# Kicker.net
KiCad netlist of a schematic drawn in Altium Designer
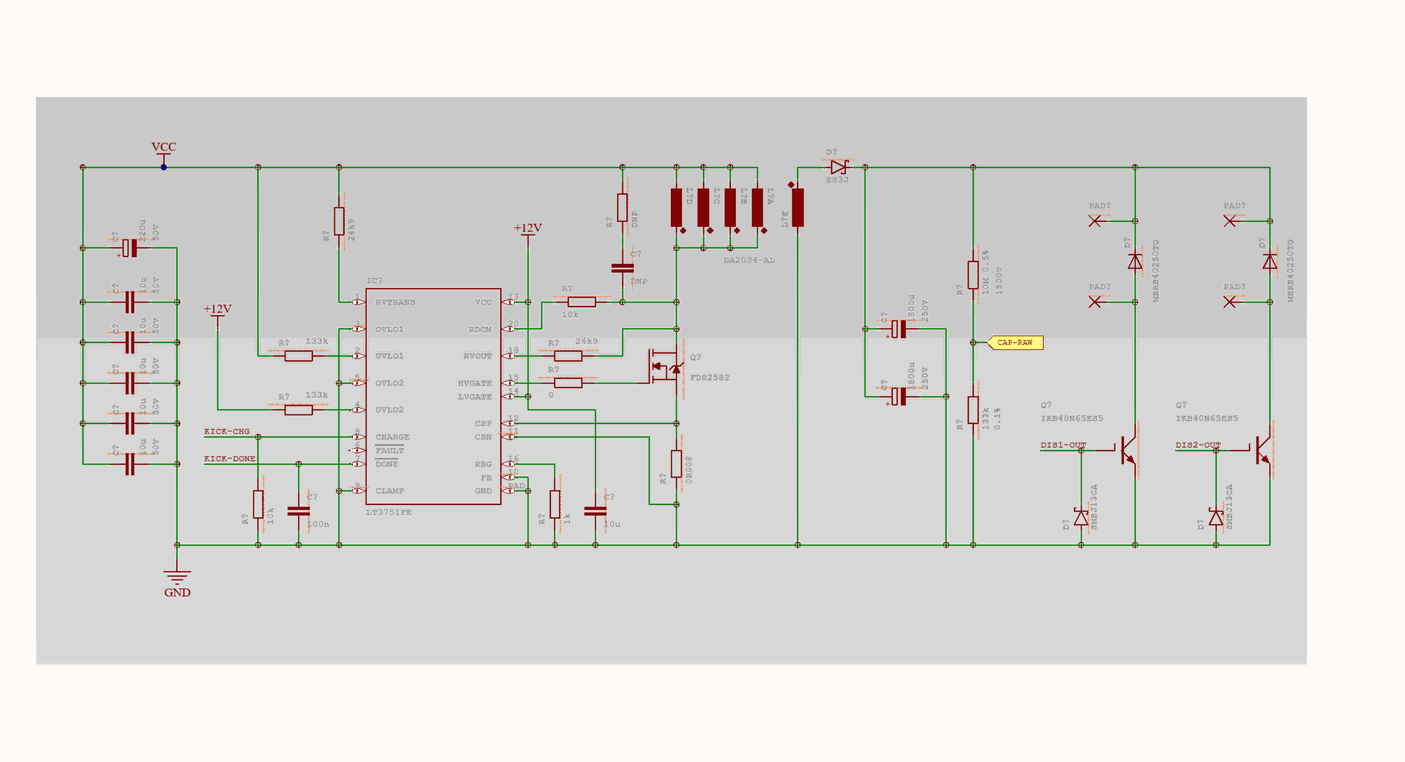
[diagram p0: Kicker.SchDoc, left]
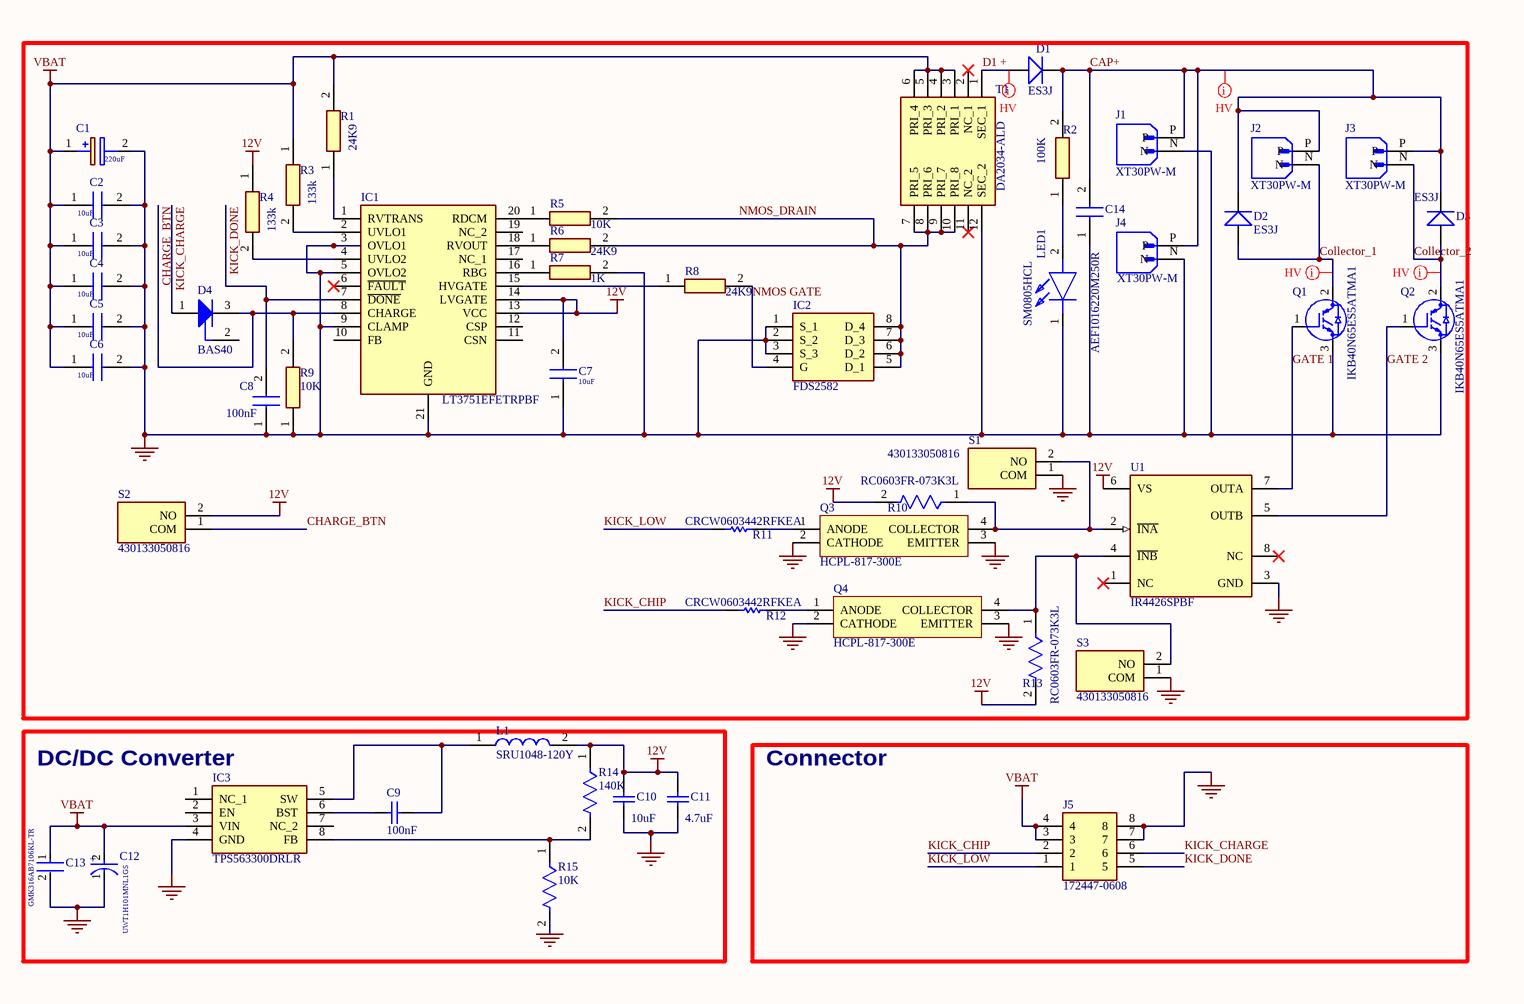
[diagram p1: Kicker.SchDoc, right]

(export (version "E")
  (design (tool "Eeschema 10.0.6"))
  (components
    (comp (ref "C1")
      (value "220uF")
      (footprint "SamacSys:CAPAE1030X1050N")
      (description "Capacitor Polarised")
      (fields
        (field (name "MANUFACTURER_PART_NUMBER") "865080657018")
        (field (name "MOUSER PART NUMBER") "710-865080657018")
      )
      (libsource (lib "*") (part "865080657018"))
    )
    (comp (ref "C2")
      (value "10uF")
      (footprint "SamacSys:CAPC2012X145N")
      (description "Capacitor 10u")
      (fields
        (field (name "MANUFACTURER_PART_NUMBER") "GRM21BR61H106KE43L")
        (field (name "MOUSER PART NUMBER") "81-GRM21BR61H106KE3L")
      )
      (libsource (lib "*") (part "GRM21BR61H106KE43L"))
    )
    (comp (ref "C3")
      (value "10uF")
      (footprint "SamacSys:CAPC2012X145N")
      (description "Capacitor 10u")
      (fields
        (field (name "MANUFACTURER_PART_NUMBER") "GRM21BR61H106KE43L")
        (field (name "MOUSER PART NUMBER") "81-GRM21BR61H106KE3L")
      )
      (libsource (lib "*") (part "GRM21BR61H106KE43L"))
    )
    (comp (ref "C4")
      (value "10uF")
      (footprint "SamacSys:CAPC2012X145N")
      (description "Capacitor 10u")
      (fields
        (field (name "MANUFACTURER_PART_NUMBER") "GRM21BR61H106KE43L")
        (field (name "MOUSER PART NUMBER") "81-GRM21BR61H106KE3L")
      )
      (libsource (lib "*") (part "GRM21BR61H106KE43L"))
    )
    (comp (ref "C5")
      (value "10uF")
      (footprint "SamacSys:CAPC2012X145N")
      (description "Capacitor 10u")
      (fields
        (field (name "MANUFACTURER_PART_NUMBER") "GRM21BR61H106KE43L")
        (field (name "MOUSER PART NUMBER") "81-GRM21BR61H106KE3L")
      )
      (libsource (lib "*") (part "GRM21BR61H106KE43L"))
    )
    (comp (ref "C6")
      (value "10uF")
      (footprint "SamacSys:CAPC2012X145N")
      (description "Capacitor 10u")
      (fields
        (field (name "MANUFACTURER_PART_NUMBER") "GRM21BR61H106KE43L")
        (field (name "MOUSER PART NUMBER") "81-GRM21BR61H106KE3L")
      )
      (libsource (lib "*") (part "GRM21BR61H106KE43L"))
    )
    (comp (ref "C7")
      (value "10uF")
      (footprint "SamacSys:CAPC2012X145N")
      (description "Capacitor 10u")
      (fields
        (field (name "MANUFACTURER_PART_NUMBER") "GRM21BR61H106KE43L")
        (field (name "MOUSER PART NUMBER") "81-GRM21BR61H106KE3L")
      )
      (libsource (lib "*") (part "GRM21BR61H106KE43L"))
    )
    (comp (ref "C8")
      (value "100nF")
      (footprint "SamacSys:CAPC1608X95N")
      (description "Capacitor")
      (fields
        (field (name "MANUFACTURER_PART_NUMBER") "C0603C104K1RACAUTO")
        (field (name "MOUSER PART NUMBER") "80-C0603C104K1RAUTO")
      )
      (libsource (lib "*") (part "C0603C104K1RACAUTO"))
    )
    (comp (ref "C9")
      (value "100nF")
      (footprint "CAPC0805(2012)155_L")
      (description "CAP 10uF 6.3V ±10% 0805 (2012 Metric) Thickness 1.55mm SMD")
      (fields (field (name "TOLERANCE") "Â±10%"))
      (libsource (lib "Altium Content Vault") (part "CAP"))
    )
    (comp (ref "C10")
      (value "10uF")
      (footprint "CAPC0805(2012)155_L")
      (description "CAP 10uF 6.3V ±10% 0805 (2012 Metric) Thickness 1.55mm SMD")
      (fields (field (name "TOLERANCE") "Â±10%"))
      (libsource (lib "Altium Content Vault") (part "CAP"))
    )
    (comp (ref "C11")
      (value "4.7uF")
      (footprint "CAPC0805(2012)155_L")
      (description "CAP 10uF 6.3V ±10% 0805 (2012 Metric) Thickness 1.55mm SMD")
      (fields (field (name "TOLERANCE") "Â±10%"))
      (libsource (lib "Altium Content Vault") (part "CAP"))
    )
    (comp (ref "C12")
      (value "UWT1H101MNL1GS")
      (footprint "FP-UWT1H101MNL1GS-MFG")
      (description "CAP ALUM 100UF 20% 50V SMD")
      (fields (field (name "TOLERANCE") "20%") (field (name "VOLTAGE") "50V"))
      (libsource (lib "Altium Content Vault") (part "203bc49f2ac43e59fd269a8c329ed05"))
    )
    (comp (ref "C13")
      (value "GMK316AB7106KL-TR")
      (footprint "FP-1206-L_3_2_0_2-W_1_6_0-IPC_C")
      (description "None")
      (fields (field (name "TOLERANCE") "10%"))
      (libsource (lib "Altium Content Vault") (part "b4654b650e69147ec39a6b967a45e02"))
    )
    (comp (ref "C14")
      (value "AEF1016220M250R")
      (footprint "roboime:CAPAE1030X1700N")
      (description "Capacitor")
      (fields (field (name "MOUSER PART NUMBER") "581-AEF1016220M250R"))
      (libsource (lib "roboime") (part "AEF1016220M250R"))
    )
    (comp (ref "D1") (value "ES3J") (footprint "Diode") (libsource (lib "roboime") (part "ES3J")))
    (comp (ref "D2") (value "ES3J") (footprint "Diode") (libsource (lib "roboime") (part "ES3J")))
    (comp (ref "D3") (value "ES3J") (footprint "Diode") (libsource (lib "roboime") (part "ES3J")))
    (comp (ref "D4")
      (value "BAS40")
      (footprint "INF-SOT23_L")
      (description "Silicon Schottky Diode, -55 to 150 degC, SOT23, Reel, Green")
      (fields (field (name "MANUFACTURER") "Infineon"))
      (libsource (lib "Altium Content Vault") (part "INF-D_A1K3-3"))
    )
    (comp (ref "IC1")
      (value "LT3751EFETRPBF")
      (footprint "SamacSys:SOP65P640X120-21N")
      (description "Integrated Circuit")
      (libsource (lib "*") (part "LT3751EFETRPBF"))
    )
    (comp (ref "IC2")
      (value "FDS2582")
      (footprint "SamacSys:SOIC127P600X175-8N")
      (description "Integrated Circuit")
      (fields (field (name "MOUSER PART NUMBER") "512-FDS2582"))
      (libsource (lib "*") (part "FDS2582"))
    )
    (comp (ref "IC3")
      (value "TPS563300DRLR")
      (footprint "roboime:SOTFL50P160X60-8N")
      (description "Integrated Circuit")
      (fields (field (name "MOUSER PART NUMBER") "595-TPS563300DRLR"))
      (libsource (lib "roboime") (part "TPS563300DRLR"))
    )
    (comp (ref "J1")
      (value "XT30PW-M")
      (footprint "AMASS_XT30PW-M")
      (description "Socket; DC supply; XT30; male; PIN: 2; on PCBs; THT; Colour: yellow")
      (fields (field (name "MF") "AMASS"))
      (libsource (lib "roboime") (part "XT30PW-M"))
    )
    (comp (ref "J2")
      (value "XT30PW-M")
      (footprint "AMASS_XT30PW-M")
      (description "Socket; DC supply; XT30; male; PIN: 2; on PCBs; THT; Colour: yellow")
      (fields (field (name "MF") "AMASS"))
      (libsource (lib "roboime") (part "XT30PW-M"))
    )
    (comp (ref "J3")
      (value "XT30PW-M")
      (footprint "AMASS_XT30PW-M")
      (description "Socket; DC supply; XT30; male; PIN: 2; on PCBs; THT; Colour: yellow")
      (fields (field (name "MF") "AMASS"))
      (libsource (lib "roboime") (part "XT30PW-M"))
    )
    (comp (ref "J4")
      (value "XT30PW-M")
      (footprint "AMASS_XT30PW-M")
      (description "Socket; DC supply; XT30; male; PIN: 2; on PCBs; THT; Colour: yellow")
      (fields (field (name "MF") "AMASS"))
      (libsource (lib "roboime") (part "XT30PW-M"))
    )
    (comp (ref "J5")
      (value "172447-0608")
      (footprint "roboime:172447-YY08")
      (description "Connector")
      (fields (field (name "MOUSER PART NUMBER") "538-172447-0608"))
      (libsource (lib "roboime") (part "172447-0608"))
    )
    (comp (ref "L1")
      (value "SRU1048-120Y")
      (footprint "roboime:INDP100100X51N")
      (description "Inductor 12uH 4A")
      (fields
        (field (name "MANUFACTURER_PART_NUMBER") "CLF7045T-4R7N-D")
        (field (name "MOUSER PART NUMBER") "810-CLF7045T-4R7N-D")
      )
      (libsource (lib "roboime") (part "SRU1048-120Y"))
    )
    (comp (ref "LED1")
      (value "SM0805HCL")
      (footprint "roboime:LEDC2012X105N")
      (description "LED")
      (fields (field (name "MOUSER PART NUMBER") "749-SM0805HCL"))
      (libsource (lib "roboime") (part "SM0805HCL"))
    )
    (comp (ref "Q1")
      (value "IKB40N65ES5ATMA1")
      (footprint "roboime:BTS141TCBUMA1")
      (description "Transistor IGBT")
      (fields (field (name "MOUSER PART NUMBER") "726-IKB40N65ES5ATMA1"))
      (libsource (lib "roboime") (part "IKB40N65ES5ATMA1"))
    )
    (comp (ref "Q2")
      (value "IKB40N65ES5ATMA1")
      (footprint "roboime:BTS141TCBUMA1")
      (description "Transistor IGBT")
      (fields (field (name "MOUSER PART NUMBER") "726-IKB40N65ES5ATMA1"))
      (libsource (lib "roboime") (part "IKB40N65ES5ATMA1"))
    )
    (comp (ref "Q3")
      (value "HCPL-817-300E")
      (footprint "roboime:HCPL-817-300")
      (libsource (lib "roboime") (part "HCPL-817-300E"))
    )
    (comp (ref "Q4")
      (value "HCPL-817-300E")
      (footprint "roboime:HCPL-817-300")
      (libsource (lib "roboime") (part "HCPL-817-300E"))
    )
    (comp (ref "R1")
      (value "24K9")
      (footprint "SamacSys:ERJS03J155V")
      (description "Resistor")
      (fields
        (field (name "MANUFACTURER_PART_NUMBER") "ERJ-U03F2492V")
        (field (name "MOUSER PART NUMBER") "667-ERJ-U03F2492V")
      )
      (libsource (lib "*") (part "ERJ-U03F2492V"))
    )
    (comp (ref "R2")
      (value "100K")
      (footprint "SamacSys:RESC1608X55N")
      (description "Resistor")
      (fields
        (field (name "MANUFACTURER_PART_NUMBER") "CPF0603F100KC1")
        (field (name "MOUSER PART NUMBER") "279-CPF0603F100KC1")
      )
      (libsource (lib "*") (part "CPF0603F100KC1"))
    )
    (comp (ref "R3")
      (value "133k")
      (footprint "SamacSys:ERJUP3")
      (description "Resistor")
      (fields
        (field (name "MANUFACTURER_PART_NUMBER") "ERJ-UP3F1333V")
        (field (name "MOUSER PART NUMBER") "667-ERJ-UP3F1333V")
      )
      (libsource (lib "*") (part "ERJ-UP3F1333V"))
    )
    (comp (ref "R4")
      (value "133k")
      (footprint "SamacSys:ERJUP3")
      (description "Resistor")
      (fields
        (field (name "MANUFACTURER_PART_NUMBER") "ERJ-UP3F1333V")
        (field (name "MOUSER PART NUMBER") "667-ERJ-UP3F1333V")
      )
      (libsource (lib "*") (part "ERJ-UP3F1333V"))
    )
    (comp (ref "R5")
      (value "10K")
      (footprint "SamacSys:RESC1608X55N")
      (description "Resistor")
      (fields
        (field (name "MANUFACTURER_PART_NUMBER") "ERJ-U3RD1002V")
        (field (name "MOUSER PART NUMBER") "667-ERJ-U3RD1002V")
      )
      (libsource (lib "") (part "ERJ-U3RD1002V_1"))
    )
    (comp (ref "R6")
      (value "24K9")
      (footprint "SamacSys:ERJS03J155V")
      (description "Resistor")
      (fields
        (field (name "MANUFACTURER_PART_NUMBER") "ERJ-U03F2492V")
        (field (name "MOUSER PART NUMBER") "667-ERJ-U03F2492V")
      )
      (libsource (lib "") (part "ERJ-U03F2492V_1"))
    )
    (comp (ref "R7")
      (value "1K")
      (footprint "SamacSys:RESC1608X55N")
      (description "Resistor")
      (fields
        (field (name "MANUFACTURER_PART_NUMBER") "CHP0603QFX-1001ELF")
        (field (name "MOUSER PART NUMBER") "652-CHP0603QFX-1001E")
      )
      (libsource (lib "*") (part "CHP0603QFX-1001ELF"))
    )
    (comp (ref "R8")
      (value "24K9")
      (footprint "SamacSys:ERJS03J155V")
      (description "Resistor")
      (fields
        (field (name "MANUFACTURER_PART_NUMBER") "ERJ-U03F2492V")
        (field (name "MOUSER PART NUMBER") "667-ERJ-U03F2492V")
      )
      (libsource (lib "") (part "ERJ-U03F2492V_1"))
    )
    (comp (ref "R9")
      (value "10K")
      (footprint "SamacSys:RESC1608X55N")
      (description "Resistor")
      (fields
        (field (name "MANUFACTURER_PART_NUMBER") "ERJ-U3RD1002V")
        (field (name "MOUSER PART NUMBER") "667-ERJ-U3RD1002V")
      )
      (libsource (lib "*") (part "ERJ-U3RD1002V"))
    )
    (comp (ref "R10")
      (value "RC0603FR-073K3L")
      (footprint "FP-RC0603-0_55-MFG")
      (fields (field (name "TOLERANCE") "1%"))
      (libsource (lib "Altium Content Vault") (part "1029c3af85768c4190bb7ad29bc67b5"))
    )
    (comp (ref "R11")
      (value "CRCW0603442RFKEA")
      (footprint "RESC1609X50X30ML10T20")
      (fields (field (name "MANUFACTURER") "Vishay Dale"))
      (libsource (lib "Altium Content Vault") (part "RES"))
    )
    (comp (ref "R12")
      (value "CRCW0603442RFKEA")
      (footprint "RESC1609X50X30ML10T20")
      (fields (field (name "MANUFACTURER") "Vishay Dale"))
      (libsource (lib "Altium Content Vault") (part "RES"))
    )
    (comp (ref "R13")
      (value "RC0603FR-073K3L")
      (footprint "FP-RC0603-0_55-MFG")
      (fields (field (name "TOLERANCE") "1%"))
      (libsource (lib "Altium Content Vault") (part "1029c3af85768c4190bb7ad29bc67b5"))
    )
    (comp (ref "R14")
      (value "140K")
      (footprint "FP-CRCW0805-e3-MFG")
      (description "RES Thick Film, 30kΩ, 1%, 0.125W, 100ppm/°C, 0805")
      (fields (field (name "TOLERANCE") "1%"))
      (libsource (lib "Altium Content Vault") (part "1029c3af85768c4190bb7ad29bc67b5"))
    )
    (comp (ref "R15")
      (value "10K")
      (footprint "FP-CRCW0805-e3-IPC_A")
      (description "RES Thick Film, 10kΩ, 1%, 0.125W, 100ppm/°C, 0805")
      (fields (field (name "TOLERANCE") "1%"))
      (libsource (lib "Altium Content Vault") (part "1029c3af85768c4190bb7ad29bc67b5"))
    )
    (comp (ref "S1")
      (value "430133050816")
      (footprint "SamacSys:430133050816")
      (description "Switch")
      (fields (field (name "MOUSER PART NUMBER") "710-430133050816"))
      (libsource (lib "roboime") (part "430133050816"))
    )
    (comp (ref "S2")
      (value "430133050816")
      (footprint "SamacSys:430133050816")
      (description "Switch")
      (fields (field (name "MOUSER PART NUMBER") "710-430133050816"))
      (libsource (lib "roboime") (part "430133050816"))
    )
    (comp (ref "S3")
      (value "430133050816")
      (footprint "SamacSys:430133050816")
      (description "Switch")
      (fields (field (name "MOUSER PART NUMBER") "710-430133050816"))
      (libsource (lib "roboime") (part "430133050816"))
    )
    (comp (ref "T1")
      (value "DA2034-ALD")
      (footprint "SamacSys:SOP300P3000X1143-12N")
      (description "Transformer")
      (fields (field (name "MOUSER PART NUMBER") "994-DA2034-ALD"))
      (libsource (lib "*") (part "DA2034-ALD"))
    )
    (comp (ref "U1")
      (value "IR4426SPBF")
      (footprint "FP-PG-DSO-8-MFG")
      (description "IC GATE DRVR LOW-SIDE 8SOIC")
      (libsource (lib "Altium Content Vault") (part "283eb03ded679e5ad24fb8acc9adf19"))
    )
  )
  (nets
    (net (code "1") (name "/CAP+") (class "Default")
      (node (ref "C14") (pin "2") (pinfunction "-_2") (pintype "passive"))
      (node (ref "D1") (pin "D1+") (pinfunction "D1+_D1+") (pintype "passive"))
      (node (ref "D2") (pin "D1+") (pinfunction "D1+_D1+") (pintype "passive"))
      (node (ref "D3") (pin "D1+") (pinfunction "D1+_D1+") (pintype "passive"))
      (node (ref "J1") (pin "P") (pinfunction "P_P") (pintype "power_in"))
      (node (ref "J2") (pin "P") (pinfunction "P_P") (pintype "power_in"))
      (node (ref "J3") (pin "P") (pinfunction "P_P") (pintype "power_in"))
      (node (ref "J4") (pin "P") (pinfunction "P_P") (pintype "power_in"))
      (node (ref "R2") (pin "2") (pinfunction "2_2") (pintype "passive"))
    )
    (net (code "2") (name "/CHARGE_BTN") (class "Default")
      (node (ref "D4") (pin "3") (pinfunction "K_3") (pintype "passive"))
      (node (ref "IC1") (pin "8") (pinfunction "CHARGE_8") (pintype "passive"))
      (node (ref "R9") (pin "2") (pinfunction "2_2") (pintype "passive"))
      (node (ref "S2") (pin "1") (pinfunction "COM_1") (pintype "passive"))
    )
    (net (code "3") (name "/Collector_1") (class "Default")
      (node (ref "D2") (pin "D1-") (pinfunction "D1-_D1-") (pintype "passive"))
      (node (ref "J2") (pin "N") (pinfunction "N_N") (pintype "power_in"))
      (node (ref "Q1") (pin "2") (pinfunction "C_2") (pintype "passive"))
    )
    (net (code "4") (name "/Collector_2") (class "Default")
      (node (ref "D3") (pin "D1-") (pinfunction "D1-_D1-") (pintype "passive"))
      (node (ref "J3") (pin "N") (pinfunction "N_N") (pintype "power_in"))
      (node (ref "Q2") (pin "2") (pinfunction "C_2") (pintype "passive"))
    )
    (net (code "5") (name "/D1 +") (class "Default")
      (node (ref "D1") (pin "D1-") (pinfunction "D1-_D1-") (pintype "passive"))
      (node (ref "T1") (pin "1") (pinfunction "SEC_1_1") (pintype "passive"))
    )
    (net (code "6") (name "/GATE 1") (class "Default")
      (node (ref "Q1") (pin "1") (pinfunction "G_1") (pintype "passive"))
      (node (ref "U1") (pin "7") (pinfunction "OUTA_7") (pintype "passive"))
    )
    (net (code "7") (name "/GATE 2") (class "Default")
      (node (ref "Q2") (pin "1") (pinfunction "G_1") (pintype "passive"))
      (node (ref "U1") (pin "5") (pinfunction "OUTB_5") (pintype "passive"))
    )
    (net (code "8") (name "/KICK_CHARGE") (class "Default")
      (node (ref "D4") (pin "1") (pinfunction "A_1") (pintype "passive"))
      (node (ref "J5") (pin "6") (pinfunction "6_6") (pintype "passive"))
    )
    (net (code "9") (name "/KICK_CHIP") (class "Default")
      (node (ref "J5") (pin "2") (pinfunction "2_2") (pintype "passive"))
      (node (ref "R12") (pin "1") (pinfunction "1_1") (pintype "passive"))
    )
    (net (code "10") (name "/KICK_DONE") (class "Default")
      (node (ref "C8") (pin "2") (pinfunction "2_2") (pintype "passive"))
      (node (ref "IC1") (pin "7") (pinfunction "~{DONE}_7") (pintype "passive"))
      (node (ref "J5") (pin "5") (pinfunction "5_5") (pintype "passive"))
    )
    (net (code "11") (name "/KICK_LOW") (class "Default")
      (node (ref "J5") (pin "1") (pinfunction "1_1") (pintype "passive"))
      (node (ref "R11") (pin "1") (pinfunction "1_1") (pintype "passive"))
    )
    (net (code "12") (name "/NMOS GATE") (class "Default")
      (node (ref "IC2") (pin "4") (pinfunction "G_4") (pintype "passive"))
      (node (ref "R8") (pin "2") (pinfunction "2_2") (pintype "passive"))
    )
    (net (code "13") (name "/NMOS_DRAIN") (class "Default")
      (node (ref "IC2") (pin "5") (pinfunction "D_1_5") (pintype "passive"))
      (node (ref "IC2") (pin "6") (pinfunction "D_2_6") (pintype "passive"))
      (node (ref "IC2") (pin "7") (pinfunction "D_3_7") (pintype "passive"))
      (node (ref "IC2") (pin "8") (pinfunction "D_4_8") (pintype "passive"))
      (node (ref "R5") (pin "2") (pinfunction "2_2") (pintype "passive"))
      (node (ref "R6") (pin "2") (pinfunction "2_2") (pintype "passive"))
      (node (ref "T1") (pin "10") (pinfunction "PRI_8_10") (pintype "passive"))
      (node (ref "T1") (pin "7") (pinfunction "PRI_5_7") (pintype "passive"))
      (node (ref "T1") (pin "8") (pinfunction "PRI_6_8") (pintype "passive"))
      (node (ref "T1") (pin "9") (pinfunction "PRI_7_9") (pintype "passive"))
    )
    (net (code "14") (name "12V") (class "Default")
      (node (ref "C10") (pin "2") (pinfunction "2_2") (pintype "passive"))
      (node (ref "C11") (pin "2") (pinfunction "2_2") (pintype "passive"))
      (node (ref "C7") (pin "2") (pinfunction "2_2") (pintype "passive"))
      (node (ref "IC1") (pin "13") (pinfunction "VCC_13") (pintype "passive"))
      (node (ref "IC1") (pin "14") (pinfunction "LVGATE_14") (pintype "passive"))
      (node (ref "L1") (pin "2") (pinfunction "2_2") (pintype "passive"))
      (node (ref "R10") (pin "2") (pinfunction "2_2") (pintype "passive"))
      (node (ref "R13") (pin "2") (pinfunction "2_2") (pintype "passive"))
      (node (ref "R14") (pin "1") (pinfunction "1_1") (pintype "passive"))
      (node (ref "R4") (pin "1") (pinfunction "1_1") (pintype "passive"))
      (node (ref "S2") (pin "2") (pinfunction "NO_2") (pintype "passive"))
      (node (ref "U1") (pin "6") (pinfunction "VS_6") (pintype "power_in"))
    )
    (net (code "15") (name "GND") (class "Default")
      (node (ref "C1") (pin "2") (pinfunction "-_2") (pintype "passive"))
      (node (ref "C10") (pin "1") (pinfunction "1_1") (pintype "passive"))
      (node (ref "C11") (pin "1") (pinfunction "1_1") (pintype "passive"))
      (node (ref "C12") (pin "1") (pinfunction "C_1") (pintype "passive"))
      (node (ref "C13") (pin "2") (pinfunction "2_2") (pintype "passive"))
      (node (ref "C14") (pin "1") (pinfunction "+_1") (pintype "passive"))
      (node (ref "C2") (pin "2") (pinfunction "2_2") (pintype "passive"))
      (node (ref "C3") (pin "2") (pinfunction "2_2") (pintype "passive"))
      (node (ref "C4") (pin "2") (pinfunction "2_2") (pintype "passive"))
      (node (ref "C5") (pin "2") (pinfunction "2_2") (pintype "passive"))
      (node (ref "C6") (pin "2") (pinfunction "2_2") (pintype "passive"))
      (node (ref "C7") (pin "1") (pinfunction "1_1") (pintype "passive"))
      (node (ref "C8") (pin "1") (pinfunction "1_1") (pintype "passive"))
      (node (ref "IC1") (pin "21") (pinfunction "GND_21") (pintype "passive"))
      (node (ref "IC1") (pin "3") (pinfunction "OVLO1_3") (pintype "passive"))
      (node (ref "IC1") (pin "5") (pinfunction "OVLO2_5") (pintype "passive"))
      (node (ref "IC1") (pin "9") (pinfunction "CLAMP_9") (pintype "passive"))
      (node (ref "IC2") (pin "1") (pinfunction "S_1_1") (pintype "passive"))
      (node (ref "IC2") (pin "2") (pinfunction "S_2_2") (pintype "passive"))
      (node (ref "IC2") (pin "3") (pinfunction "S_3_3") (pintype "passive"))
      (node (ref "IC3") (pin "4") (pinfunction "GND_4") (pintype "passive"))
      (node (ref "J1") (pin "N") (pinfunction "N_N") (pintype "power_in"))
      (node (ref "J4") (pin "N") (pinfunction "N_N") (pintype "power_in"))
      (node (ref "J5") (pin "7") (pinfunction "7_7") (pintype "passive"))
      (node (ref "J5") (pin "8") (pinfunction "8_8") (pintype "passive"))
      (node (ref "LED1") (pin "1") (pinfunction "K_1") (pintype "passive"))
      (node (ref "Q1") (pin "3") (pinfunction "E_3") (pintype "passive"))
      (node (ref "Q2") (pin "3") (pinfunction "E_3") (pintype "passive"))
      (node (ref "Q3") (pin "2") (pinfunction "CATHODE_2") (pintype "passive"))
      (node (ref "Q3") (pin "3") (pinfunction "EMITTER_3") (pintype "passive"))
      (node (ref "Q4") (pin "2") (pinfunction "CATHODE_2") (pintype "passive"))
      (node (ref "Q4") (pin "3") (pinfunction "EMITTER_3") (pintype "passive"))
      (node (ref "R15") (pin "2") (pinfunction "2_2") (pintype "passive"))
      (node (ref "R7") (pin "2") (pinfunction "2_2") (pintype "passive"))
      (node (ref "R9") (pin "1") (pinfunction "1_1") (pintype "passive"))
      (node (ref "S1") (pin "1") (pinfunction "COM_1") (pintype "passive"))
      (node (ref "S3") (pin "1") (pinfunction "COM_1") (pintype "passive"))
      (node (ref "T1") (pin "12") (pinfunction "SEC_2_12") (pintype "passive"))
      (node (ref "U1") (pin "3") (pinfunction "GND_3") (pintype "power_in"))
    )
    (net (code "16") (name "Net-(IC1-HVGATE)") (class "Default")
      (node (ref "IC1") (pin "15") (pinfunction "HVGATE_15") (pintype "passive"))
      (node (ref "R8") (pin "1") (pinfunction "1_1") (pintype "passive"))
    )
    (net (code "17") (name "Net-(IC1-RBG)") (class "Default")
      (node (ref "IC1") (pin "16") (pinfunction "RBG_16") (pintype "passive"))
      (node (ref "R7") (pin "1") (pinfunction "1_1") (pintype "passive"))
    )
    (net (code "18") (name "Net-(IC1-RDCM)") (class "Default")
      (node (ref "IC1") (pin "20") (pinfunction "RDCM_20") (pintype "passive"))
      (node (ref "R5") (pin "1") (pinfunction "1_1") (pintype "passive"))
    )
    (net (code "19") (name "Net-(IC1-RVOUT)") (class "Default")
      (node (ref "IC1") (pin "18") (pinfunction "RVOUT_18") (pintype "passive"))
      (node (ref "R6") (pin "1") (pinfunction "1_1") (pintype "passive"))
    )
    (net (code "20") (name "Net-(IC1-RVTRANS)") (class "Default")
      (node (ref "IC1") (pin "1") (pinfunction "RVTRANS_1") (pintype "passive"))
      (node (ref "R1") (pin "1") (pinfunction "1_1") (pintype "passive"))
    )
    (net (code "21") (name "Net-(IC1-UVLO1)") (class "Default")
      (node (ref "IC1") (pin "2") (pinfunction "UVLO1_2") (pintype "passive"))
      (node (ref "R3") (pin "2") (pinfunction "2_2") (pintype "passive"))
    )
    (net (code "22") (name "Net-(IC1-UVLO2)") (class "Default")
      (node (ref "IC1") (pin "4") (pinfunction "UVLO2_4") (pintype "passive"))
      (node (ref "R4") (pin "2") (pinfunction "2_2") (pintype "passive"))
    )
    (net (code "23") (name "Net-(IC3-BST)") (class "Default")
      (node (ref "C9") (pin "2") (pinfunction "2_2") (pintype "passive"))
      (node (ref "IC3") (pin "6") (pinfunction "BST_6") (pintype "passive"))
    )
    (net (code "24") (name "Net-(IC3-FB)") (class "Default")
      (node (ref "IC3") (pin "8") (pinfunction "FB_8") (pintype "passive"))
      (node (ref "R14") (pin "2") (pinfunction "2_2") (pintype "passive"))
      (node (ref "R15") (pin "1") (pinfunction "1_1") (pintype "passive"))
    )
    (net (code "25") (name "Net-(IC3-SW)") (class "Default")
      (node (ref "C9") (pin "1") (pinfunction "1_1") (pintype "passive"))
      (node (ref "IC3") (pin "5") (pinfunction "SW_5") (pintype "passive"))
      (node (ref "L1") (pin "1") (pinfunction "1_1") (pintype "passive"))
    )
    (net (code "26") (name "Net-(LED1-A)") (class "Default")
      (node (ref "LED1") (pin "2") (pinfunction "A_2") (pintype "passive"))
      (node (ref "R2") (pin "1") (pinfunction "1_1") (pintype "passive"))
    )
    (net (code "27") (name "Net-(Q3-ANODE)") (class "Default")
      (node (ref "Q3") (pin "1") (pinfunction "ANODE_1") (pintype "passive"))
      (node (ref "R11") (pin "2") (pinfunction "2_2") (pintype "passive"))
    )
    (net (code "28") (name "Net-(Q3-COLLECTOR)") (class "Default")
      (node (ref "Q3") (pin "4") (pinfunction "COLLECTOR_4") (pintype "passive"))
      (node (ref "R10") (pin "1") (pinfunction "1_1") (pintype "passive"))
      (node (ref "S1") (pin "2") (pinfunction "NO_2") (pintype "passive"))
      (node (ref "U1") (pin "2") (pinfunction "~{INA}_2") (pintype "input"))
    )
    (net (code "29") (name "Net-(Q4-ANODE)") (class "Default")
      (node (ref "Q4") (pin "1") (pinfunction "ANODE_1") (pintype "passive"))
      (node (ref "R12") (pin "2") (pinfunction "2_2") (pintype "passive"))
    )
    (net (code "30") (name "Net-(Q4-COLLECTOR)") (class "Default")
      (node (ref "Q4") (pin "4") (pinfunction "COLLECTOR_4") (pintype "passive"))
      (node (ref "R13") (pin "1") (pinfunction "1_1") (pintype "passive"))
      (node (ref "S3") (pin "2") (pinfunction "NO_2") (pintype "passive"))
      (node (ref "U1") (pin "4") (pinfunction "~{INB}_4") (pintype "passive"))
    )
    (net (code "31") (name "VBAT") (class "Default")
      (node (ref "C1") (pin "1") (pinfunction "+_1") (pintype "passive"))
      (node (ref "C12") (pin "2") (pinfunction "A_2") (pintype "passive"))
      (node (ref "C13") (pin "1") (pinfunction "1_1") (pintype "passive"))
      (node (ref "C2") (pin "1") (pinfunction "1_1") (pintype "passive"))
      (node (ref "C3") (pin "1") (pinfunction "1_1") (pintype "passive"))
      (node (ref "C4") (pin "1") (pinfunction "1_1") (pintype "passive"))
      (node (ref "C5") (pin "1") (pinfunction "1_1") (pintype "passive"))
      (node (ref "C6") (pin "1") (pinfunction "1_1") (pintype "passive"))
      (node (ref "IC3") (pin "3") (pinfunction "VIN_3") (pintype "passive"))
      (node (ref "J5") (pin "3") (pinfunction "3_3") (pintype "passive"))
      (node (ref "J5") (pin "4") (pinfunction "4_4") (pintype "passive"))
      (node (ref "R1") (pin "2") (pinfunction "2_2") (pintype "passive"))
      (node (ref "R3") (pin "1") (pinfunction "1_1") (pintype "passive"))
      (node (ref "T1") (pin "3") (pinfunction "PRI_1_3") (pintype "passive"))
      (node (ref "T1") (pin "4") (pinfunction "PRI_2_4") (pintype "passive"))
      (node (ref "T1") (pin "5") (pinfunction "PRI_3_5") (pintype "passive"))
      (node (ref "T1") (pin "6") (pinfunction "PRI_4_6") (pintype "passive"))
    )
    (net (code "32") (name "unconnected-(D4-NC-Pad2)") (class "Default")
      (node (ref "D4") (pin "2") (pinfunction "NC_2") (pintype "passive"))
    )
    (net (code "33") (name "unconnected-(IC1-CSN-Pad11)") (class "Default")
      (node (ref "IC1") (pin "11") (pinfunction "CSN_11") (pintype "passive"))
    )
    (net (code "34") (name "unconnected-(IC1-CSP-Pad12)") (class "Default")
      (node (ref "IC1") (pin "12") (pinfunction "CSP_12") (pintype "passive"))
    )
    (net (code "35") (name "unconnected-(IC1-FB-Pad10)") (class "Default")
      (node (ref "IC1") (pin "10") (pinfunction "FB_10") (pintype "passive"))
    )
    (net (code "36") (name "unconnected-(IC1-NC_1-Pad17)") (class "Default")
      (node (ref "IC1") (pin "17") (pinfunction "NC_1_17") (pintype "passive"))
    )
    (net (code "37") (name "unconnected-(IC1-NC_2-Pad19)") (class "Default")
      (node (ref "IC1") (pin "19") (pinfunction "NC_2_19") (pintype "passive"))
    )
    (net (code "38") (name "unconnected-(IC1-~{FAULT}-Pad6)") (class "Default")
      (node (ref "IC1") (pin "6") (pinfunction "~{FAULT}_6") (pintype "passive+no_connect"))
    )
    (net (code "39") (name "unconnected-(IC3-EN-Pad2)") (class "Default")
      (node (ref "IC3") (pin "2") (pinfunction "EN_2") (pintype "passive"))
    )
    (net (code "40") (name "unconnected-(IC3-NC_1-Pad1)") (class "Default")
      (node (ref "IC3") (pin "1") (pinfunction "NC_1_1") (pintype "passive"))
    )
    (net (code "41") (name "unconnected-(IC3-NC_2-Pad7)") (class "Default")
      (node (ref "IC3") (pin "7") (pinfunction "NC_2_7") (pintype "passive"))
    )
    (net (code "42") (name "unconnected-(T1-NC_1-Pad2)") (class "Default")
      (node (ref "T1") (pin "2") (pinfunction "NC_1_2") (pintype "passive+no_connect"))
    )
    (net (code "43") (name "unconnected-(T1-NC_2-Pad11)") (class "Default")
      (node (ref "T1") (pin "11") (pinfunction "NC_2_11") (pintype "passive+no_connect"))
    )
    (net (code "44") (name "unconnected-(U1-NC-Pad1)") (class "Default")
      (node (ref "U1") (pin "1") (pinfunction "NC_1") (pintype "passive+no_connect"))
    )
    (net (code "45") (name "unconnected-(U1-NC-Pad8)") (class "Default")
      (node (ref "U1") (pin "8") (pinfunction "NC_8") (pintype "passive+no_connect"))
    )
  )
)
